# AST1021.net
KiCad netlist of a schematic drawn in EAGLE
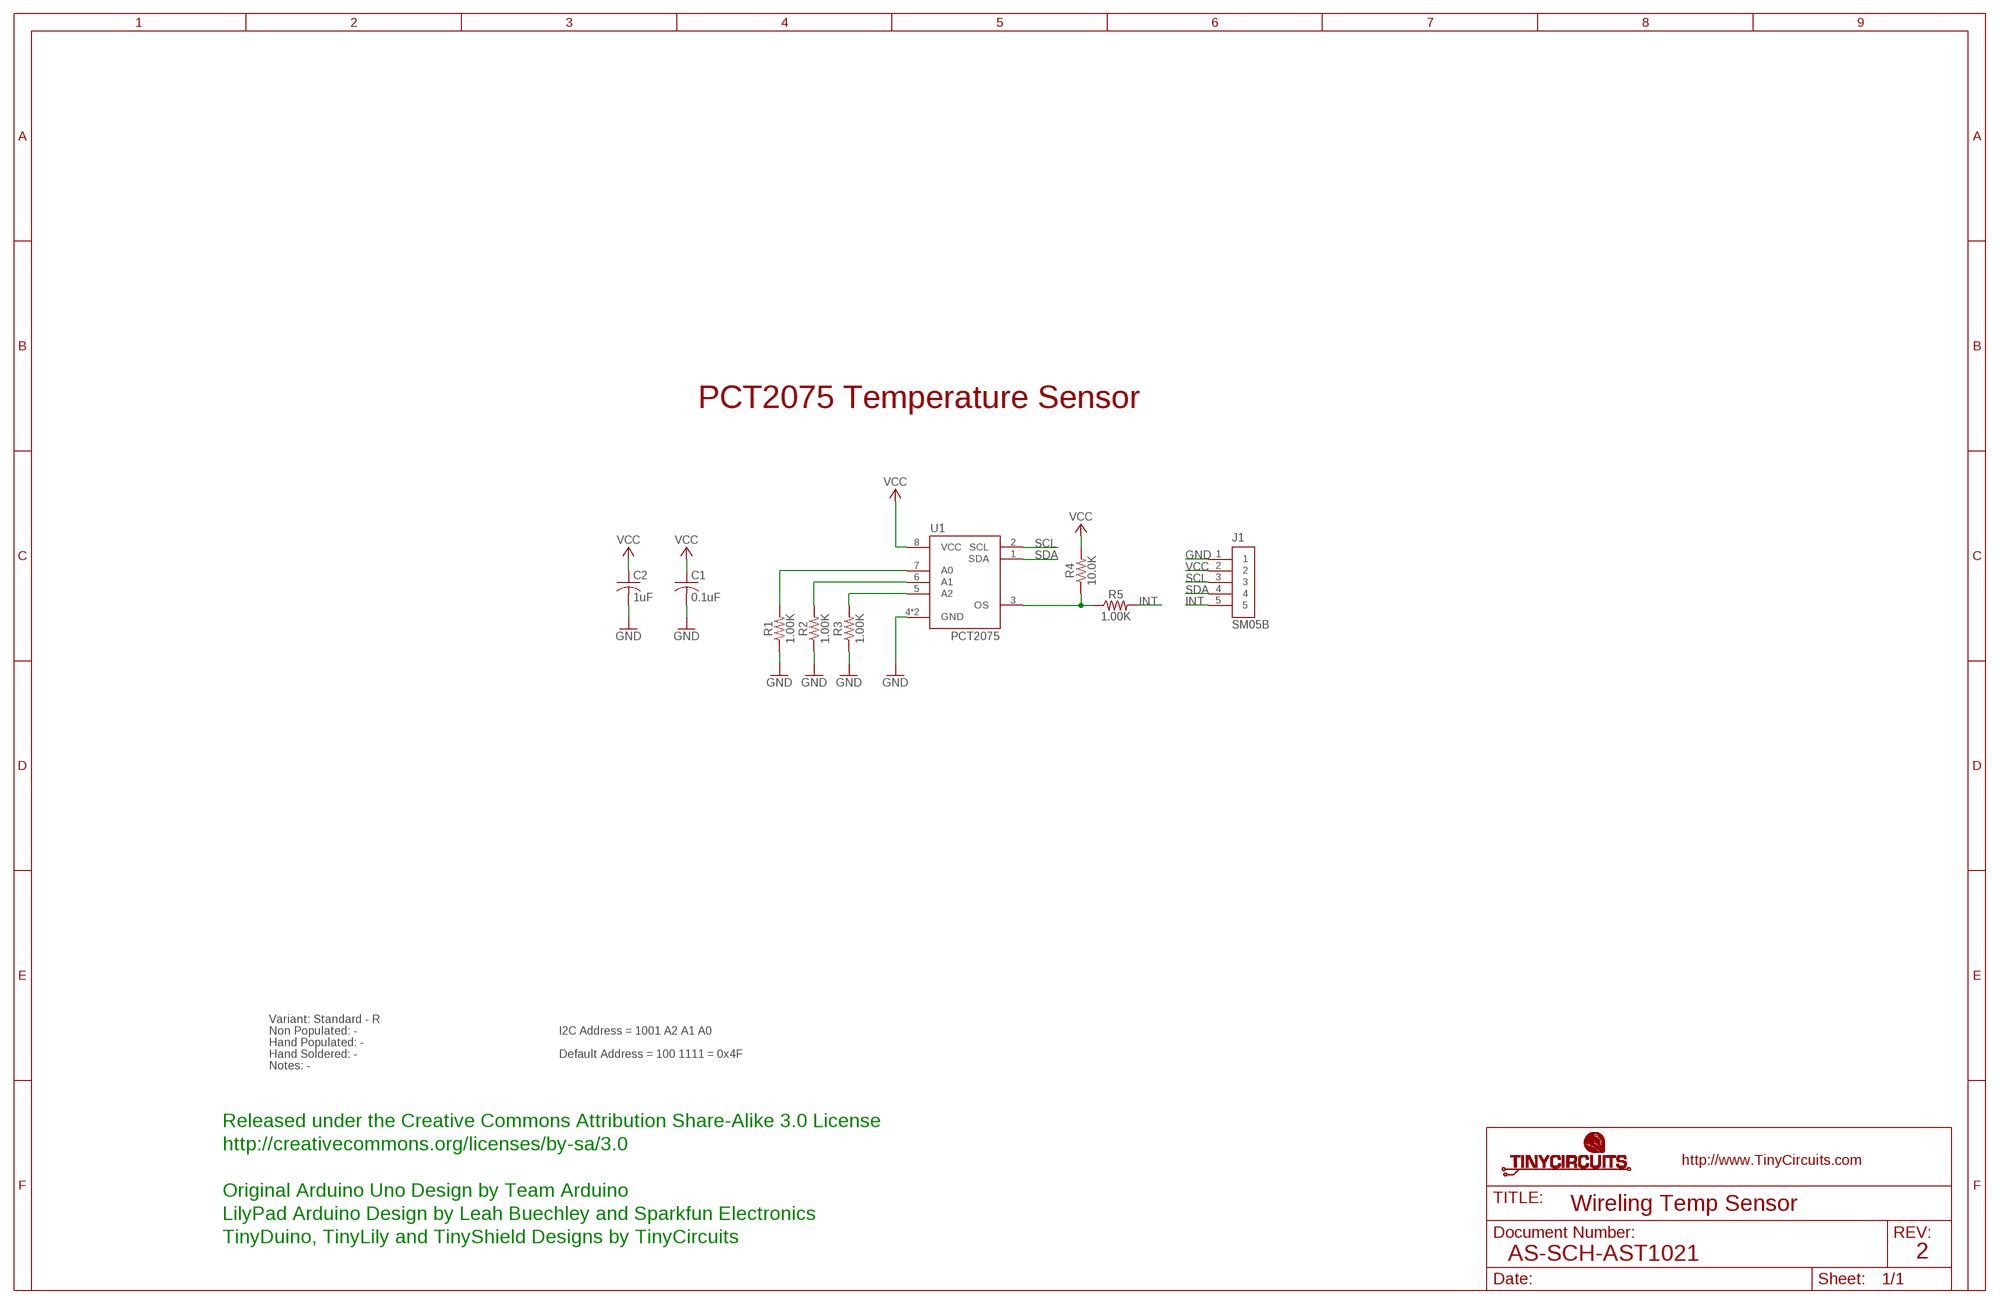
[diagram p0: schematic, sheet 1]

(export (version "E")
  (design (tool "Eeschema 10.0.6"))
  (components
    (comp (ref "C1")
      (value "0.1uF")
      (footprint "eagle-import:C0402")
      (fields (field (name "PARTNO") "AS-ITM-00008"))
      (libsource (lib "eagle-import") (part "AS-ITM-00008"))
    )
    (comp (ref "C2")
      (value "1uF")
      (footprint "eagle-import:C0603")
      (fields (field (name "PARTNO") "AS-ITM-00410") (field (name "PARTNO_1") "AS-ITM-00410"))
      (libsource (lib "eagle-import") (part "AS-ITM-00410"))
    )
    (comp (ref "J1")
      (value "SM05B")
      (footprint "eagle-import:JST_SH_5X1_EDGE")
      (fields (field (name "PARTNO") "AS-ITM-00340"))
      (libsource (lib "eagle-import") (part "AS-ITM-00340EDGE"))
    )
    (comp (ref "R1")
      (value "1.00K")
      (footprint "eagle-import:0402")
      (fields (field (name "PARTNO") "AS-ITM-00003") (field (name "PARTNO_1") "AS-ITM-00003"))
      (libsource (lib "eagle-import") (part "AS-ITM-00003"))
    )
    (comp (ref "R2")
      (value "1.00K")
      (footprint "eagle-import:0402")
      (fields (field (name "PARTNO") "AS-ITM-00003") (field (name "PARTNO_1") "AS-ITM-00003"))
      (libsource (lib "eagle-import") (part "AS-ITM-00003"))
    )
    (comp (ref "R3")
      (value "1.00K")
      (footprint "eagle-import:0402")
      (fields (field (name "PARTNO") "AS-ITM-00003") (field (name "PARTNO_1") "AS-ITM-00003"))
      (libsource (lib "eagle-import") (part "AS-ITM-00003"))
    )
    (comp (ref "R4")
      (value "10.0K")
      (footprint "eagle-import:0402")
      (fields (field (name "PARTNO") "AS-ITM-00032"))
      (libsource (lib "eagle-import") (part "AS-ITM-00032"))
    )
    (comp (ref "R5")
      (value "1.00K")
      (footprint "eagle-import:0402")
      (fields (field (name "PARTNO") "AS-ITM-00003") (field (name "PARTNO_1") "AS-ITM-00003"))
      (libsource (lib "eagle-import") (part "AS-ITM-00003"))
    )
    (comp (ref "U1")
      (value "PCT2075")
      (footprint "eagle-import:HWSON-8")
      (fields (field (name "PARTNO") "AS-ITM-00325"))
      (libsource (lib "eagle-import") (part "AS-ITM-00325"))
    )
  )
  (nets
    (net (code "1") (name "/INT") (class "Default")
      (node (ref "J1") (pin "5") (pinfunction "5_5") (pintype "bidirectional"))
      (node (ref "R5") (pin "2") (pinfunction "2_2") (pintype "passive"))
    )
    (net (code "2") (name "/SCL") (class "Default")
      (node (ref "J1") (pin "3") (pinfunction "3_3") (pintype "bidirectional"))
      (node (ref "U1") (pin "2") (pinfunction "SCL_2") (pintype "bidirectional"))
    )
    (net (code "3") (name "/SDA") (class "Default")
      (node (ref "J1") (pin "4") (pinfunction "4_4") (pintype "bidirectional"))
      (node (ref "U1") (pin "1") (pinfunction "SDA_1") (pintype "bidirectional"))
    )
    (net (code "4") (name "GND") (class "Default")
      (node (ref "C1") (pin "2") (pinfunction "2_2") (pintype "passive"))
      (node (ref "C2") (pin "2") (pinfunction "2_2") (pintype "passive"))
      (node (ref "J1") (pin "1") (pinfunction "1_1") (pintype "bidirectional"))
      (node (ref "R1") (pin "1") (pinfunction "1_1") (pintype "passive"))
      (node (ref "R2") (pin "1") (pinfunction "1_1") (pintype "passive"))
      (node (ref "R3") (pin "1") (pinfunction "1_1") (pintype "passive"))
      (node (ref "U1") (pin "4") (pinfunction "GND_4") (pintype "bidirectional"))
      (node (ref "U1") (pin "GND") (pinfunction "GND_GND") (pintype "bidirectional"))
    )
    (net (code "5") (name "Net-(U1-A0)") (class "Default")
      (node (ref "R1") (pin "2") (pinfunction "2_2") (pintype "passive"))
      (node (ref "U1") (pin "7") (pinfunction "A0_7") (pintype "bidirectional"))
    )
    (net (code "6") (name "Net-(U1-A1)") (class "Default")
      (node (ref "R2") (pin "2") (pinfunction "2_2") (pintype "passive"))
      (node (ref "U1") (pin "6") (pinfunction "A1_6") (pintype "bidirectional"))
    )
    (net (code "7") (name "Net-(U1-A2)") (class "Default")
      (node (ref "R3") (pin "2") (pinfunction "2_2") (pintype "passive"))
      (node (ref "U1") (pin "5") (pinfunction "A2_5") (pintype "bidirectional"))
    )
    (net (code "8") (name "Net-(U1-OS)") (class "Default")
      (node (ref "R4") (pin "1") (pinfunction "1_1") (pintype "passive"))
      (node (ref "R5") (pin "1") (pinfunction "1_1") (pintype "passive"))
      (node (ref "U1") (pin "3") (pinfunction "OS_3") (pintype "bidirectional"))
    )
    (net (code "9") (name "VCC") (class "Default")
      (node (ref "C1") (pin "1") (pinfunction "1_1") (pintype "passive"))
      (node (ref "C2") (pin "1") (pinfunction "1_1") (pintype "passive"))
      (node (ref "J1") (pin "2") (pinfunction "2_2") (pintype "bidirectional"))
      (node (ref "R4") (pin "2") (pinfunction "2_2") (pintype "passive"))
      (node (ref "U1") (pin "8") (pinfunction "VCC_8") (pintype "bidirectional"))
    )
  )
)
